# MicroMultimeter_PROBE_Sch.net
KiCad netlist of a schematic drawn in Altium Designer
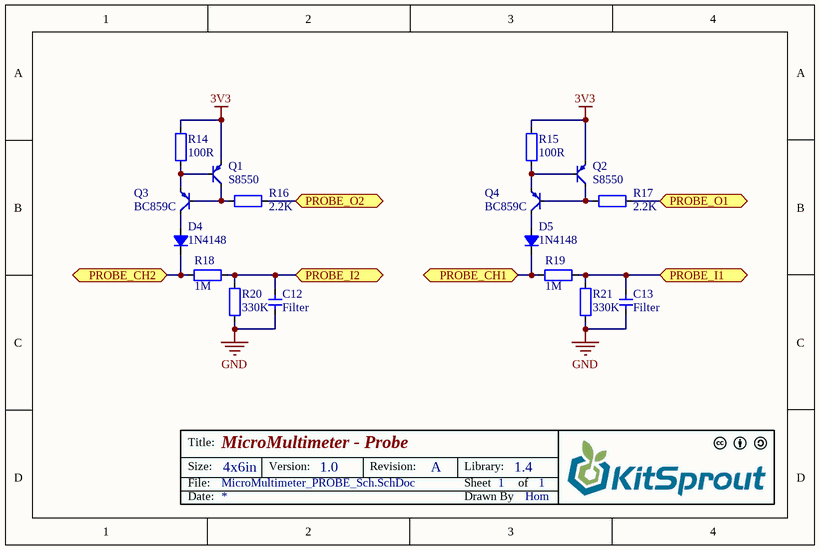
[diagram p0: MicroMultimeter_PROBE_Sch.SchDoc]

(export (version "E")
  (design (tool "Eeschema 10.0.6"))
  (components
    (comp (ref "C12")
      (value "Filter")
      (footprint "PCB_PassiveCap:CAP_0603")
      (description "Capacitor")
      (fields (field (name "Comment") "Cap_0603"))
      (libsource (lib "SCH_Passive") (part "Cap_0603"))
    )
    (comp (ref "C13")
      (value "Filter")
      (footprint "PCB_PassiveCap:CAP_0603")
      (description "Capacitor")
      (fields (field (name "Comment") "Cap_0603"))
      (libsource (lib "SCH_Passive") (part "Cap_0603"))
    )
    (comp (ref "D4")
      (value "1N4148")
      (footprint "PCB_ActiveDIO:SOD323")
      (description "Diode")
      (fields (field (name "Comment") "Diode_SOD323"))
      (libsource (lib "SCH_Active") (part "Diode_SOD323"))
    )
    (comp (ref "D5")
      (value "1N4148")
      (footprint "PCB_ActiveDIO:SOD323")
      (description "Diode")
      (fields (field (name "Comment") "Diode_SOD323"))
      (libsource (lib "SCH_Active") (part "Diode_SOD323"))
    )
    (comp (ref "Q1")
      (value "S8550")
      (footprint "PCB_IntegratedCircuit:SOT23-3")
      (description "Transistor")
      (fields (field (name "Comment") "BJT_PNP"))
      (libsource (lib "SCH_Active") (part "BJT_PNP"))
    )
    (comp (ref "Q2")
      (value "S8550")
      (footprint "PCB_IntegratedCircuit:SOT23-3")
      (description "Transistor")
      (fields (field (name "Comment") "BJT_PNP"))
      (libsource (lib "SCH_Active") (part "BJT_PNP"))
    )
    (comp (ref "Q3")
      (value "BC859C")
      (footprint "PCB_IntegratedCircuit:SOT23-3")
      (description "Transistor")
      (fields (field (name "Comment") "BJT_PNP"))
      (libsource (lib "SCH_Active") (part "BJT_PNP"))
    )
    (comp (ref "Q4")
      (value "BC859C")
      (footprint "PCB_IntegratedCircuit:SOT23-3")
      (description "Transistor")
      (fields (field (name "Comment") "BJT_PNP"))
      (libsource (lib "SCH_Active") (part "BJT_PNP"))
    )
    (comp (ref "R14")
      (value "100R")
      (footprint "PCB_PassiveRes:RES_0603")
      (description "Resistor")
      (fields (field (name "Comment") "Res_0603"))
      (libsource (lib "SCH_Passive") (part "Res_0603"))
    )
    (comp (ref "R15")
      (value "100R")
      (footprint "PCB_PassiveRes:RES_0603")
      (description "Resistor")
      (fields (field (name "Comment") "Res_0603"))
      (libsource (lib "SCH_Passive") (part "Res_0603"))
    )
    (comp (ref "R16")
      (value "2.2K")
      (footprint "PCB_PassiveRes:RES_0603")
      (description "Resistor")
      (fields (field (name "Comment") "Res_0603"))
      (libsource (lib "") (part "Res_0603_1"))
    )
    (comp (ref "R17")
      (value "2.2K")
      (footprint "PCB_PassiveRes:RES_0603")
      (description "Resistor")
      (fields (field (name "Comment") "Res_0603"))
      (libsource (lib "") (part "Res_0603_1"))
    )
    (comp (ref "R18")
      (value "1M")
      (footprint "PCB_PassiveRes:RES_0603")
      (description "Resistor")
      (fields (field (name "Comment") "Res_0603"))
      (libsource (lib "") (part "Res_0603_1"))
    )
    (comp (ref "R19")
      (value "1M")
      (footprint "PCB_PassiveRes:RES_0603")
      (description "Resistor")
      (fields (field (name "Comment") "Res_0603"))
      (libsource (lib "") (part "Res_0603_1"))
    )
    (comp (ref "R20")
      (value "330K")
      (footprint "PCB_PassiveRes:RES_0603")
      (description "Resistor")
      (fields (field (name "Comment") "Res_0603"))
      (libsource (lib "SCH_Passive") (part "Res_0603"))
    )
    (comp (ref "R21")
      (value "330K")
      (footprint "PCB_PassiveRes:RES_0603")
      (description "Resistor")
      (fields (field (name "Comment") "Res_0603"))
      (libsource (lib "SCH_Passive") (part "Res_0603"))
    )
  )
  (nets
    (net (code "1") (name "/PROBE_CH1") (class "Default")
      (node (ref "D5") (pin "2") (pinfunction "K_2") (pintype "passive"))
      (node (ref "R19") (pin "2") (pinfunction "2_2") (pintype "passive"))
    )
    (net (code "2") (name "/PROBE_CH2") (class "Default")
      (node (ref "D4") (pin "2") (pinfunction "K_2") (pintype "passive"))
      (node (ref "R18") (pin "2") (pinfunction "2_2") (pintype "passive"))
    )
    (net (code "3") (name "/PROBE_I1") (class "Default")
      (node (ref "C13") (pin "2") (pinfunction "2_2") (pintype "passive"))
      (node (ref "R19") (pin "1") (pinfunction "1_1") (pintype "passive"))
      (node (ref "R21") (pin "2") (pinfunction "2_2") (pintype "passive"))
    )
    (net (code "4") (name "/PROBE_I2") (class "Default")
      (node (ref "C12") (pin "2") (pinfunction "2_2") (pintype "passive"))
      (node (ref "R18") (pin "1") (pinfunction "1_1") (pintype "passive"))
      (node (ref "R20") (pin "2") (pinfunction "2_2") (pintype "passive"))
    )
    (net (code "5") (name "/PROBE_O1") (class "Default")
      (node (ref "R17") (pin "1") (pinfunction "1_1") (pintype "passive"))
    )
    (net (code "6") (name "/PROBE_O2") (class "Default")
      (node (ref "R16") (pin "1") (pinfunction "1_1") (pintype "passive"))
    )
    (net (code "7") (name "3V3") (class "Default")
      (node (ref "Q1") (pin "2") (pinfunction "E_2") (pintype "passive"))
      (node (ref "Q2") (pin "2") (pinfunction "E_2") (pintype "passive"))
      (node (ref "R14") (pin "2") (pinfunction "2_2") (pintype "passive"))
      (node (ref "R15") (pin "2") (pinfunction "2_2") (pintype "passive"))
    )
    (net (code "8") (name "GND") (class "Default")
      (node (ref "C12") (pin "1") (pinfunction "1_1") (pintype "passive"))
      (node (ref "C13") (pin "1") (pinfunction "1_1") (pintype "passive"))
      (node (ref "R20") (pin "1") (pinfunction "1_1") (pintype "passive"))
      (node (ref "R21") (pin "1") (pinfunction "1_1") (pintype "passive"))
    )
    (net (code "9") (name "Net-(D4-A)") (class "Default")
      (node (ref "D4") (pin "1") (pinfunction "A_1") (pintype "passive"))
      (node (ref "Q3") (pin "3") (pinfunction "C_3") (pintype "passive"))
    )
    (net (code "10") (name "Net-(D5-A)") (class "Default")
      (node (ref "D5") (pin "1") (pinfunction "A_1") (pintype "passive"))
      (node (ref "Q4") (pin "3") (pinfunction "C_3") (pintype "passive"))
    )
    (net (code "11") (name "Net-(Q1-B)") (class "Default")
      (node (ref "Q1") (pin "1") (pinfunction "B_1") (pintype "passive"))
      (node (ref "Q3") (pin "2") (pinfunction "E_2") (pintype "passive"))
      (node (ref "R14") (pin "1") (pinfunction "1_1") (pintype "passive"))
    )
    (net (code "12") (name "Net-(Q1-C)") (class "Default")
      (node (ref "Q1") (pin "3") (pinfunction "C_3") (pintype "passive"))
      (node (ref "Q3") (pin "1") (pinfunction "B_1") (pintype "passive"))
      (node (ref "R16") (pin "2") (pinfunction "2_2") (pintype "passive"))
    )
    (net (code "13") (name "Net-(Q2-B)") (class "Default")
      (node (ref "Q2") (pin "1") (pinfunction "B_1") (pintype "passive"))
      (node (ref "Q4") (pin "2") (pinfunction "E_2") (pintype "passive"))
      (node (ref "R15") (pin "1") (pinfunction "1_1") (pintype "passive"))
    )
    (net (code "14") (name "Net-(Q2-C)") (class "Default")
      (node (ref "Q2") (pin "3") (pinfunction "C_3") (pintype "passive"))
      (node (ref "Q4") (pin "1") (pinfunction "B_1") (pintype "passive"))
      (node (ref "R17") (pin "2") (pinfunction "2_2") (pintype "passive"))
    )
  )
)
